# devtool.net
KiCad netlist of a schematic drawn in EAGLE
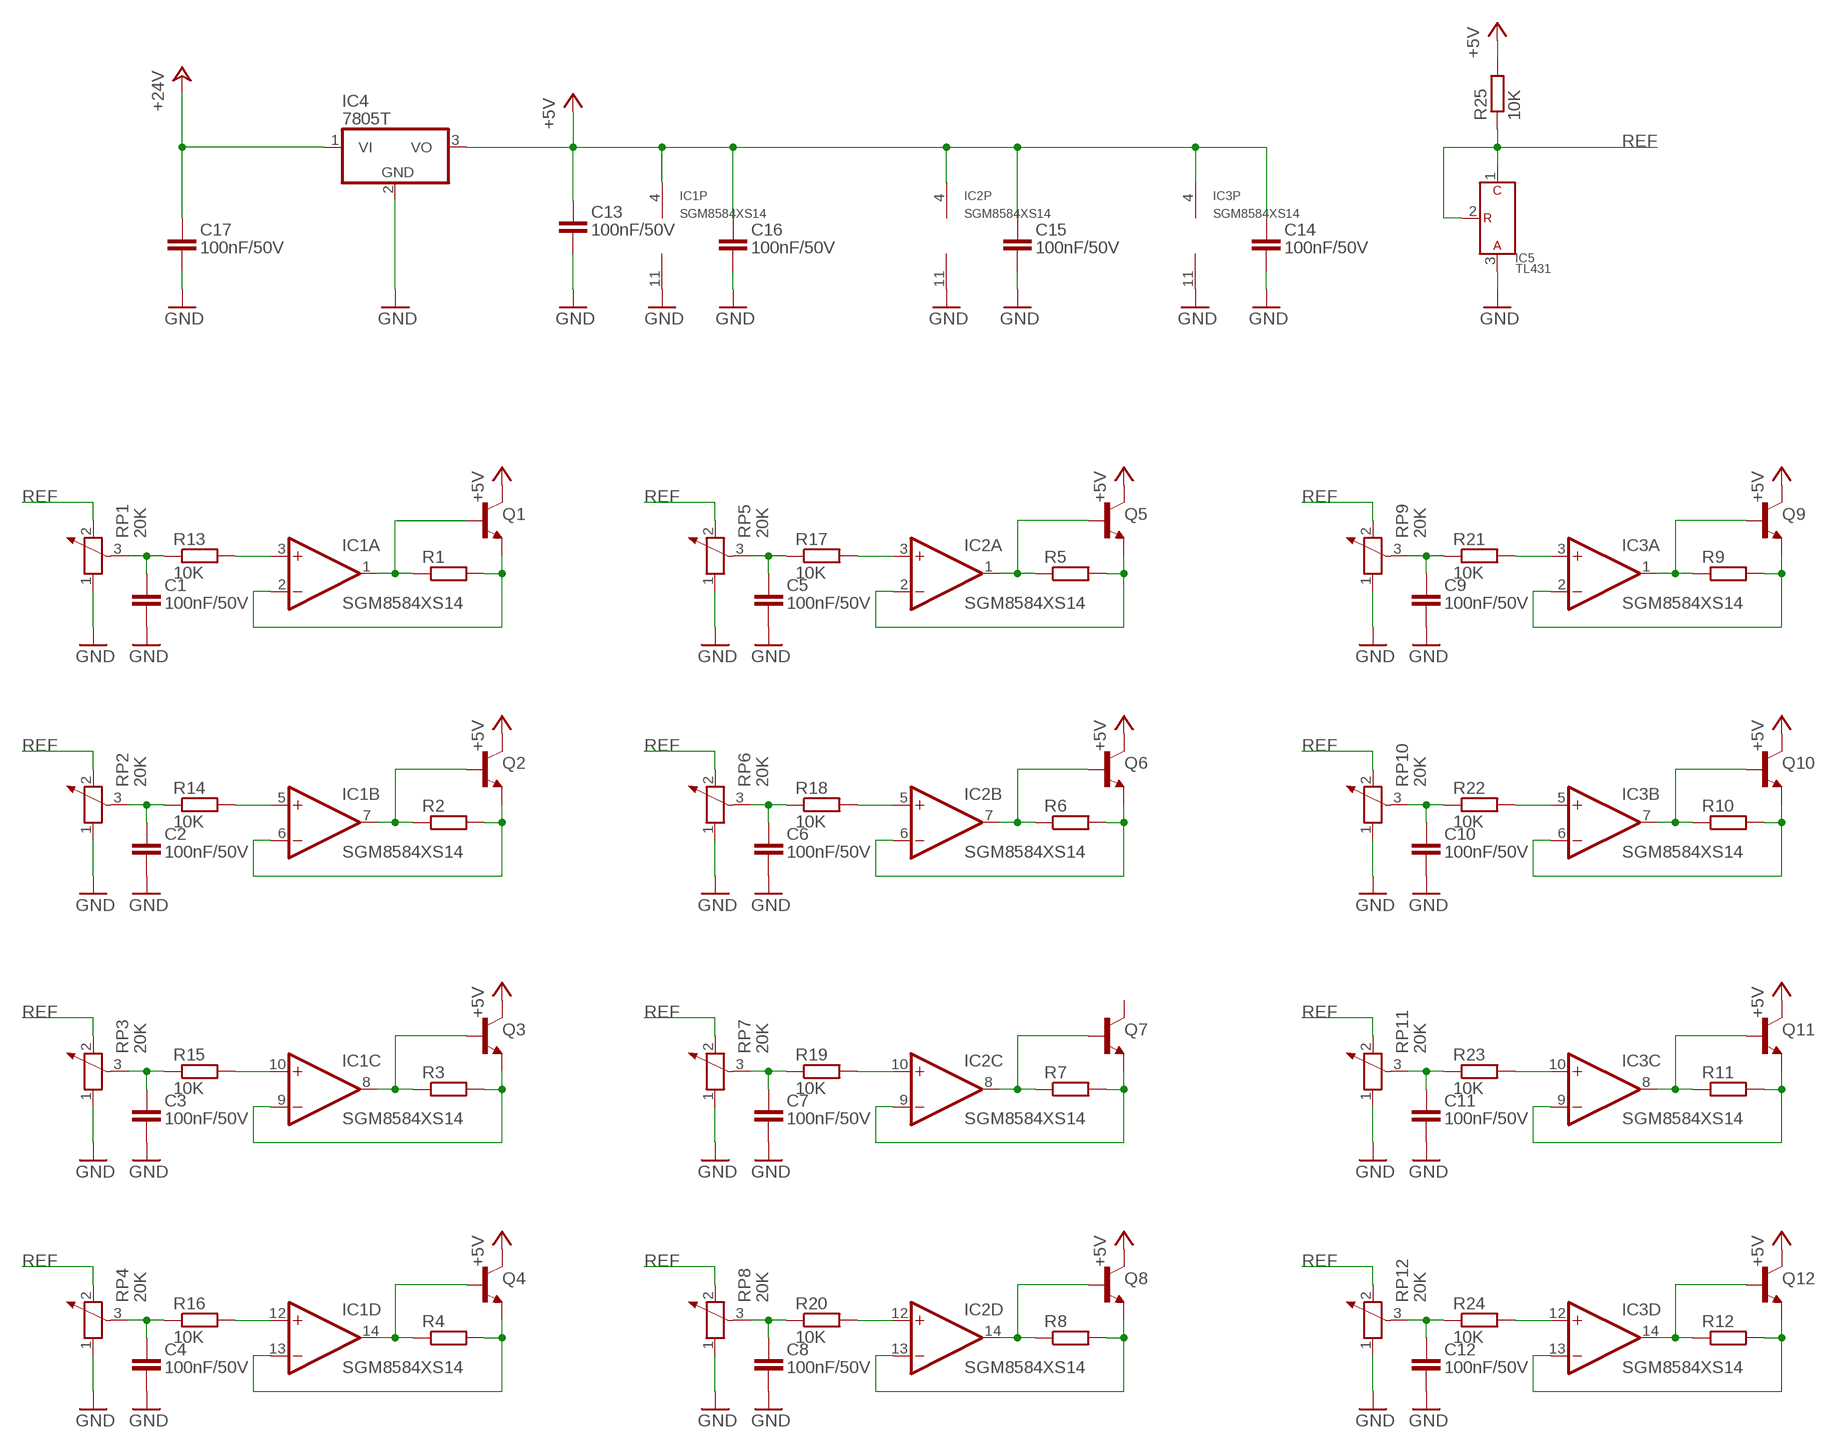
[diagram p0: schematic, sheet 1, part 1 of 2]
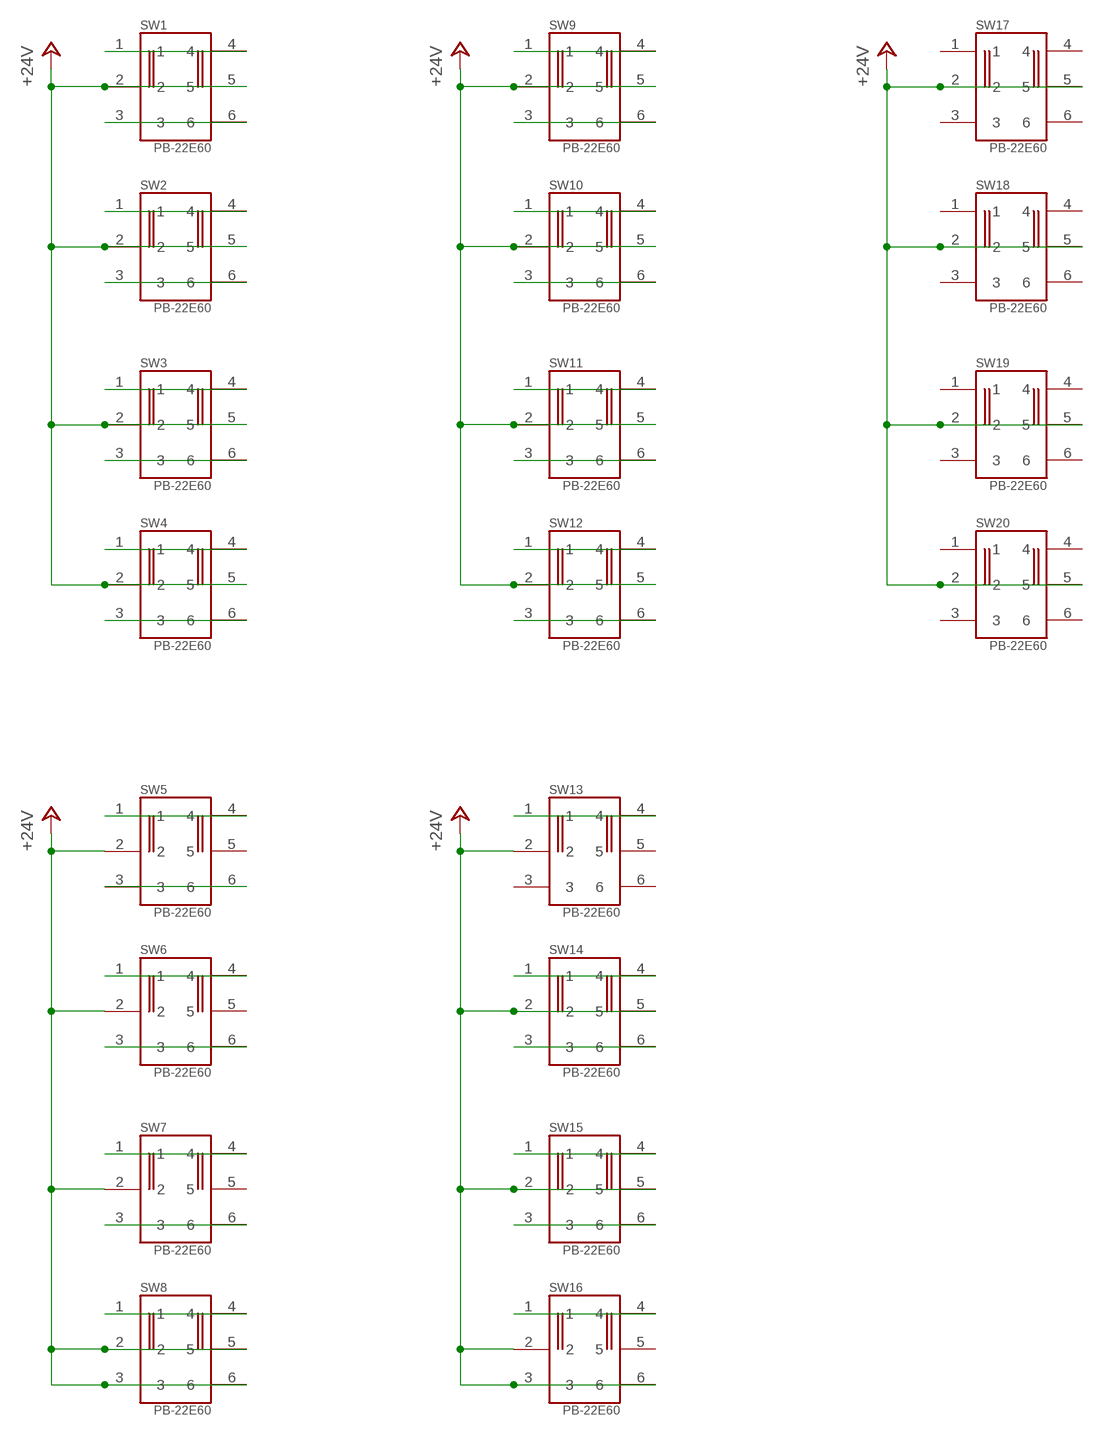
[diagram p1: schematic, sheet 1, part 2 of 2]

(export (version "E")
  (design (tool "Eeschema 10.0.6"))
  (components
    (comp (ref "C1")
      (value "100nF/50V")
      (footprint "eagle-import:C0603")
      (libsource (lib "eagle-import") (part "C0603"))
    )
    (comp (ref "C2")
      (value "100nF/50V")
      (footprint "eagle-import:C0603")
      (libsource (lib "eagle-import") (part "C0603"))
    )
    (comp (ref "C3")
      (value "100nF/50V")
      (footprint "eagle-import:C0603")
      (libsource (lib "eagle-import") (part "C0603"))
    )
    (comp (ref "C4")
      (value "100nF/50V")
      (footprint "eagle-import:C0603")
      (libsource (lib "eagle-import") (part "C0603"))
    )
    (comp (ref "C5")
      (value "100nF/50V")
      (footprint "eagle-import:C0603")
      (libsource (lib "eagle-import") (part "C0603"))
    )
    (comp (ref "C6")
      (value "100nF/50V")
      (footprint "eagle-import:C0603")
      (libsource (lib "eagle-import") (part "C0603"))
    )
    (comp (ref "C7")
      (value "100nF/50V")
      (footprint "eagle-import:C0603")
      (libsource (lib "eagle-import") (part "C0603"))
    )
    (comp (ref "C8")
      (value "100nF/50V")
      (footprint "eagle-import:C0603")
      (libsource (lib "eagle-import") (part "C0603"))
    )
    (comp (ref "C9")
      (value "100nF/50V")
      (footprint "eagle-import:C0603")
      (libsource (lib "eagle-import") (part "C0603"))
    )
    (comp (ref "C10")
      (value "100nF/50V")
      (footprint "eagle-import:C0603")
      (libsource (lib "eagle-import") (part "C0603"))
    )
    (comp (ref "C11")
      (value "100nF/50V")
      (footprint "eagle-import:C0603")
      (libsource (lib "eagle-import") (part "C0603"))
    )
    (comp (ref "C12")
      (value "100nF/50V")
      (footprint "eagle-import:C0603")
      (libsource (lib "eagle-import") (part "C0603"))
    )
    (comp (ref "C13")
      (value "100nF/50V")
      (footprint "eagle-import:C0603")
      (libsource (lib "eagle-import") (part "C0603"))
    )
    (comp (ref "C14")
      (value "100nF/50V")
      (footprint "eagle-import:C0603")
      (libsource (lib "eagle-import") (part "C0603"))
    )
    (comp (ref "C15")
      (value "100nF/50V")
      (footprint "eagle-import:C0603")
      (libsource (lib "eagle-import") (part "C0603"))
    )
    (comp (ref "C16")
      (value "100nF/50V")
      (footprint "eagle-import:C0603")
      (libsource (lib "eagle-import") (part "C0603"))
    )
    (comp (ref "C17")
      (value "100nF/50V")
      (footprint "eagle-import:C0603")
      (libsource (lib "eagle-import") (part "C0603"))
    )
    (comp (ref "IC1")
      (value "SGM8584XS14")
      (footprint "eagle-import:SOIC-14")
      (libsource (lib "eagle-import") (part "SGM8584XS14"))
    )
    (comp (ref "IC2")
      (value "SGM8584XS14")
      (footprint "eagle-import:SOIC-14")
      (libsource (lib "eagle-import") (part "SGM8584XS14"))
    )
    (comp (ref "IC3")
      (value "SGM8584XS14")
      (footprint "eagle-import:SOIC-14")
      (libsource (lib "eagle-import") (part "SGM8584XS14"))
    )
    (comp (ref "IC4")
      (value "7805T")
      (footprint "eagle-import:TO220H")
      (libsource (lib "eagle-import") (part "78T05"))
    )
    (comp (ref "IC5")
      (value "TL431")
      (footprint "eagle-import:SOT23-3")
      (libsource (lib "eagle-import") (part "TL431"))
    )
    (comp (ref "Q1")
      (value "NPN")
      (footprint "eagle-import:SOT23-BEC")
      (libsource (lib "eagle-import") (part "NPN"))
    )
    (comp (ref "Q2")
      (value "NPN")
      (footprint "eagle-import:SOT23-BEC")
      (libsource (lib "eagle-import") (part "NPN"))
    )
    (comp (ref "Q3")
      (value "NPN")
      (footprint "eagle-import:SOT23-BEC")
      (libsource (lib "eagle-import") (part "NPN"))
    )
    (comp (ref "Q4")
      (value "NPN")
      (footprint "eagle-import:SOT23-BEC")
      (libsource (lib "eagle-import") (part "NPN"))
    )
    (comp (ref "Q5")
      (value "NPN")
      (footprint "eagle-import:SOT23-BEC")
      (libsource (lib "eagle-import") (part "NPN"))
    )
    (comp (ref "Q6")
      (value "NPN")
      (footprint "eagle-import:SOT23-BEC")
      (libsource (lib "eagle-import") (part "NPN"))
    )
    (comp (ref "Q7")
      (value "NPN")
      (footprint "eagle-import:SOT23-BEC")
      (libsource (lib "eagle-import") (part "NPN"))
    )
    (comp (ref "Q8")
      (value "NPN")
      (footprint "eagle-import:SOT23-BEC")
      (libsource (lib "eagle-import") (part "NPN"))
    )
    (comp (ref "Q9")
      (value "NPN")
      (footprint "eagle-import:SOT23-BEC")
      (libsource (lib "eagle-import") (part "NPN"))
    )
    (comp (ref "Q10")
      (value "NPN")
      (footprint "eagle-import:SOT23-BEC")
      (libsource (lib "eagle-import") (part "NPN"))
    )
    (comp (ref "Q11")
      (value "NPN")
      (footprint "eagle-import:SOT23-BEC")
      (libsource (lib "eagle-import") (part "NPN"))
    )
    (comp (ref "Q12")
      (value "NPN")
      (footprint "eagle-import:SOT23-BEC")
      (libsource (lib "eagle-import") (part "NPN"))
    )
    (comp (ref "R1")
      (value "R0603")
      (footprint "eagle-import:R0603")
      (libsource (lib "eagle-import") (part "R0603"))
    )
    (comp (ref "R2")
      (value "R0603")
      (footprint "eagle-import:R0603")
      (libsource (lib "eagle-import") (part "R0603"))
    )
    (comp (ref "R3")
      (value "R0603")
      (footprint "eagle-import:R0603")
      (libsource (lib "eagle-import") (part "R0603"))
    )
    (comp (ref "R4")
      (value "R0603")
      (footprint "eagle-import:R0603")
      (libsource (lib "eagle-import") (part "R0603"))
    )
    (comp (ref "R5")
      (value "R0603")
      (footprint "eagle-import:R0603")
      (libsource (lib "eagle-import") (part "R0603"))
    )
    (comp (ref "R6")
      (value "R0603")
      (footprint "eagle-import:R0603")
      (libsource (lib "eagle-import") (part "R0603"))
    )
    (comp (ref "R7")
      (value "R0603")
      (footprint "eagle-import:R0603")
      (libsource (lib "eagle-import") (part "R0603"))
    )
    (comp (ref "R8")
      (value "R0603")
      (footprint "eagle-import:R0603")
      (libsource (lib "eagle-import") (part "R0603"))
    )
    (comp (ref "R9")
      (value "R0603")
      (footprint "eagle-import:R0603")
      (libsource (lib "eagle-import") (part "R0603"))
    )
    (comp (ref "R10")
      (value "R0603")
      (footprint "eagle-import:R0603")
      (libsource (lib "eagle-import") (part "R0603"))
    )
    (comp (ref "R11")
      (value "R0603")
      (footprint "eagle-import:R0603")
      (libsource (lib "eagle-import") (part "R0603"))
    )
    (comp (ref "R12")
      (value "R0603")
      (footprint "eagle-import:R0603")
      (libsource (lib "eagle-import") (part "R0603"))
    )
    (comp (ref "R13")
      (value "10K")
      (footprint "eagle-import:R0603")
      (libsource (lib "eagle-import") (part "R0603"))
    )
    (comp (ref "R14")
      (value "10K")
      (footprint "eagle-import:R0603")
      (libsource (lib "eagle-import") (part "R0603"))
    )
    (comp (ref "R15")
      (value "10K")
      (footprint "eagle-import:R0603")
      (libsource (lib "eagle-import") (part "R0603"))
    )
    (comp (ref "R16")
      (value "10K")
      (footprint "eagle-import:R0603")
      (libsource (lib "eagle-import") (part "R0603"))
    )
    (comp (ref "R17")
      (value "10K")
      (footprint "eagle-import:R0603")
      (libsource (lib "eagle-import") (part "R0603"))
    )
    (comp (ref "R18")
      (value "10K")
      (footprint "eagle-import:R0603")
      (libsource (lib "eagle-import") (part "R0603"))
    )
    (comp (ref "R19")
      (value "10K")
      (footprint "eagle-import:R0603")
      (libsource (lib "eagle-import") (part "R0603"))
    )
    (comp (ref "R20")
      (value "10K")
      (footprint "eagle-import:R0603")
      (libsource (lib "eagle-import") (part "R0603"))
    )
    (comp (ref "R21")
      (value "10K")
      (footprint "eagle-import:R0603")
      (libsource (lib "eagle-import") (part "R0603"))
    )
    (comp (ref "R22")
      (value "10K")
      (footprint "eagle-import:R0603")
      (libsource (lib "eagle-import") (part "R0603"))
    )
    (comp (ref "R23")
      (value "10K")
      (footprint "eagle-import:R0603")
      (libsource (lib "eagle-import") (part "R0603"))
    )
    (comp (ref "R24")
      (value "10K")
      (footprint "eagle-import:R0603")
      (libsource (lib "eagle-import") (part "R0603"))
    )
    (comp (ref "R25")
      (value "10K")
      (footprint "eagle-import:R0603")
      (libsource (lib "eagle-import") (part "R0603"))
    )
    (comp (ref "RP1")
      (value "20K")
      (footprint "eagle-import:RM065")
      (libsource (lib "eagle-import") (part "RM065"))
    )
    (comp (ref "RP2")
      (value "20K")
      (footprint "eagle-import:RM065")
      (libsource (lib "eagle-import") (part "RM065"))
    )
    (comp (ref "RP3")
      (value "20K")
      (footprint "eagle-import:RM065")
      (libsource (lib "eagle-import") (part "RM065"))
    )
    (comp (ref "RP4")
      (value "20K")
      (footprint "eagle-import:RM065")
      (libsource (lib "eagle-import") (part "RM065"))
    )
    (comp (ref "RP5")
      (value "20K")
      (footprint "eagle-import:RM065")
      (libsource (lib "eagle-import") (part "RM065"))
    )
    (comp (ref "RP6")
      (value "20K")
      (footprint "eagle-import:RM065")
      (libsource (lib "eagle-import") (part "RM065"))
    )
    (comp (ref "RP7")
      (value "20K")
      (footprint "eagle-import:RM065")
      (libsource (lib "eagle-import") (part "RM065"))
    )
    (comp (ref "RP8")
      (value "20K")
      (footprint "eagle-import:RM065")
      (libsource (lib "eagle-import") (part "RM065"))
    )
    (comp (ref "RP9")
      (value "20K")
      (footprint "eagle-import:RM065")
      (libsource (lib "eagle-import") (part "RM065"))
    )
    (comp (ref "RP10")
      (value "20K")
      (footprint "eagle-import:RM065")
      (libsource (lib "eagle-import") (part "RM065"))
    )
    (comp (ref "RP11")
      (value "20K")
      (footprint "eagle-import:RM065")
      (libsource (lib "eagle-import") (part "RM065"))
    )
    (comp (ref "RP12")
      (value "20K")
      (footprint "eagle-import:RM065")
      (libsource (lib "eagle-import") (part "RM065"))
    )
    (comp (ref "SW1")
      (value "PB-22E60")
      (footprint "eagle-import:PB-22E60")
      (libsource (lib "eagle-import") (part "PB-22E60"))
    )
    (comp (ref "SW2")
      (value "PB-22E60")
      (footprint "eagle-import:PB-22E60")
      (libsource (lib "eagle-import") (part "PB-22E60"))
    )
    (comp (ref "SW3")
      (value "PB-22E60")
      (footprint "eagle-import:PB-22E60")
      (libsource (lib "eagle-import") (part "PB-22E60"))
    )
    (comp (ref "SW4")
      (value "PB-22E60")
      (footprint "eagle-import:PB-22E60")
      (libsource (lib "eagle-import") (part "PB-22E60"))
    )
    (comp (ref "SW5")
      (value "PB-22E60")
      (footprint "eagle-import:PB-22E60")
      (libsource (lib "eagle-import") (part "PB-22E60"))
    )
    (comp (ref "SW6")
      (value "PB-22E60")
      (footprint "eagle-import:PB-22E60")
      (libsource (lib "eagle-import") (part "PB-22E60"))
    )
    (comp (ref "SW7")
      (value "PB-22E60")
      (footprint "eagle-import:PB-22E60")
      (libsource (lib "eagle-import") (part "PB-22E60"))
    )
    (comp (ref "SW8")
      (value "PB-22E60")
      (footprint "eagle-import:PB-22E60")
      (libsource (lib "eagle-import") (part "PB-22E60"))
    )
    (comp (ref "SW9")
      (value "PB-22E60")
      (footprint "eagle-import:PB-22E60")
      (libsource (lib "eagle-import") (part "PB-22E60"))
    )
    (comp (ref "SW10")
      (value "PB-22E60")
      (footprint "eagle-import:PB-22E60")
      (libsource (lib "eagle-import") (part "PB-22E60"))
    )
    (comp (ref "SW11")
      (value "PB-22E60")
      (footprint "eagle-import:PB-22E60")
      (libsource (lib "eagle-import") (part "PB-22E60"))
    )
    (comp (ref "SW12")
      (value "PB-22E60")
      (footprint "eagle-import:PB-22E60")
      (libsource (lib "eagle-import") (part "PB-22E60"))
    )
    (comp (ref "SW13")
      (value "PB-22E60")
      (footprint "eagle-import:PB-22E60")
      (libsource (lib "eagle-import") (part "PB-22E60"))
    )
    (comp (ref "SW14")
      (value "PB-22E60")
      (footprint "eagle-import:PB-22E60")
      (libsource (lib "eagle-import") (part "PB-22E60"))
    )
    (comp (ref "SW15")
      (value "PB-22E60")
      (footprint "eagle-import:PB-22E60")
      (libsource (lib "eagle-import") (part "PB-22E60"))
    )
    (comp (ref "SW16")
      (value "PB-22E60")
      (footprint "eagle-import:PB-22E60")
      (libsource (lib "eagle-import") (part "PB-22E60"))
    )
    (comp (ref "SW17")
      (value "PB-22E60")
      (footprint "eagle-import:PB-22E60")
      (libsource (lib "eagle-import") (part "PB-22E60"))
    )
    (comp (ref "SW18")
      (value "PB-22E60")
      (footprint "eagle-import:PB-22E60")
      (libsource (lib "eagle-import") (part "PB-22E60"))
    )
    (comp (ref "SW19")
      (value "PB-22E60")
      (footprint "eagle-import:PB-22E60")
      (libsource (lib "eagle-import") (part "PB-22E60"))
    )
    (comp (ref "SW20")
      (value "PB-22E60")
      (footprint "eagle-import:PB-22E60")
      (libsource (lib "eagle-import") (part "PB-22E60"))
    )
  )
  (nets
    (net (code "1") (name "+5V") (class "Default")
      (node (ref "C13") (pin "1") (pinfunction "1_1") (pintype "passive"))
      (node (ref "C14") (pin "1") (pinfunction "1_1") (pintype "passive"))
      (node (ref "C15") (pin "1") (pinfunction "1_1") (pintype "passive"))
      (node (ref "C16") (pin "1") (pinfunction "1_1") (pintype "passive"))
      (node (ref "IC1") (pin "4") (pinfunction "V+_4") (pintype "power_in"))
      (node (ref "IC2") (pin "4") (pinfunction "V+_4") (pintype "power_in"))
      (node (ref "IC3") (pin "4") (pinfunction "V+_4") (pintype "power_in"))
      (node (ref "IC4") (pin "3") (pinfunction "VO_3") (pintype "passive"))
      (node (ref "Q1") (pin "C") (pinfunction "C_C") (pintype "passive"))
      (node (ref "Q10") (pin "C") (pinfunction "C_C") (pintype "passive"))
      (node (ref "Q11") (pin "C") (pinfunction "C_C") (pintype "passive"))
      (node (ref "Q12") (pin "C") (pinfunction "C_C") (pintype "passive"))
      (node (ref "Q2") (pin "C") (pinfunction "C_C") (pintype "passive"))
      (node (ref "Q3") (pin "C") (pinfunction "C_C") (pintype "passive"))
      (node (ref "Q4") (pin "C") (pinfunction "C_C") (pintype "passive"))
      (node (ref "Q5") (pin "C") (pinfunction "C_C") (pintype "passive"))
      (node (ref "Q6") (pin "C") (pinfunction "C_C") (pintype "passive"))
      (node (ref "Q8") (pin "C") (pinfunction "C_C") (pintype "passive"))
      (node (ref "Q9") (pin "C") (pinfunction "C_C") (pintype "passive"))
      (node (ref "R25") (pin "2") (pinfunction "2_2") (pintype "passive"))
    )
    (net (code "2") (name "+24V") (class "Default")
      (node (ref "C17") (pin "1") (pinfunction "1_1") (pintype "passive"))
      (node (ref "IC4") (pin "1") (pinfunction "VI_1") (pintype "input"))
      (node (ref "SW1") (pin "2") (pinfunction "2_2") (pintype "passive"))
      (node (ref "SW1") (pin "5") (pinfunction "5_5") (pintype "passive"))
      (node (ref "SW10") (pin "2") (pinfunction "2_2") (pintype "passive"))
      (node (ref "SW10") (pin "5") (pinfunction "5_5") (pintype "passive"))
      (node (ref "SW11") (pin "2") (pinfunction "2_2") (pintype "passive"))
      (node (ref "SW11") (pin "5") (pinfunction "5_5") (pintype "passive"))
      (node (ref "SW12") (pin "2") (pinfunction "2_2") (pintype "passive"))
      (node (ref "SW12") (pin "5") (pinfunction "5_5") (pintype "passive"))
      (node (ref "SW13") (pin "2") (pinfunction "2_2") (pintype "passive"))
      (node (ref "SW14") (pin "2") (pinfunction "2_2") (pintype "passive"))
      (node (ref "SW14") (pin "5") (pinfunction "5_5") (pintype "passive"))
      (node (ref "SW15") (pin "2") (pinfunction "2_2") (pintype "passive"))
      (node (ref "SW15") (pin "5") (pinfunction "5_5") (pintype "passive"))
      (node (ref "SW16") (pin "2") (pinfunction "2_2") (pintype "passive"))
      (node (ref "SW16") (pin "3") (pinfunction "3_3") (pintype "passive"))
      (node (ref "SW16") (pin "6") (pinfunction "6_6") (pintype "passive"))
      (node (ref "SW17") (pin "2") (pinfunction "2_2") (pintype "passive"))
      (node (ref "SW17") (pin "5") (pinfunction "5_5") (pintype "passive"))
      (node (ref "SW18") (pin "2") (pinfunction "2_2") (pintype "passive"))
      (node (ref "SW18") (pin "5") (pinfunction "5_5") (pintype "passive"))
      (node (ref "SW19") (pin "2") (pinfunction "2_2") (pintype "passive"))
      (node (ref "SW19") (pin "5") (pinfunction "5_5") (pintype "passive"))
      (node (ref "SW2") (pin "2") (pinfunction "2_2") (pintype "passive"))
      (node (ref "SW2") (pin "5") (pinfunction "5_5") (pintype "passive"))
      (node (ref "SW20") (pin "2") (pinfunction "2_2") (pintype "passive"))
      (node (ref "SW20") (pin "5") (pinfunction "5_5") (pintype "passive"))
      (node (ref "SW3") (pin "2") (pinfunction "2_2") (pintype "passive"))
      (node (ref "SW3") (pin "5") (pinfunction "5_5") (pintype "passive"))
      (node (ref "SW4") (pin "2") (pinfunction "2_2") (pintype "passive"))
      (node (ref "SW4") (pin "5") (pinfunction "5_5") (pintype "passive"))
      (node (ref "SW5") (pin "2") (pinfunction "2_2") (pintype "passive"))
      (node (ref "SW6") (pin "2") (pinfunction "2_2") (pintype "passive"))
      (node (ref "SW7") (pin "2") (pinfunction "2_2") (pintype "passive"))
      (node (ref "SW8") (pin "2") (pinfunction "2_2") (pintype "passive"))
      (node (ref "SW8") (pin "3") (pinfunction "3_3") (pintype "passive"))
      (node (ref "SW8") (pin "5") (pinfunction "5_5") (pintype "passive"))
      (node (ref "SW8") (pin "6") (pinfunction "6_6") (pintype "passive"))
      (node (ref "SW9") (pin "2") (pinfunction "2_2") (pintype "passive"))
      (node (ref "SW9") (pin "5") (pinfunction "5_5") (pintype "passive"))
    )
    (net (code "3") (name "/REF") (class "Default")
      (node (ref "IC5") (pin "1") (pinfunction "C_1") (pintype "passive"))
      (node (ref "IC5") (pin "2") (pinfunction "REF_2") (pintype "passive"))
      (node (ref "R25") (pin "1") (pinfunction "1_1") (pintype "passive"))
      (node (ref "RP1") (pin "2") (pinfunction "2_2") (pintype "passive"))
      (node (ref "RP10") (pin "2") (pinfunction "2_2") (pintype "passive"))
      (node (ref "RP11") (pin "2") (pinfunction "2_2") (pintype "passive"))
      (node (ref "RP12") (pin "2") (pinfunction "2_2") (pintype "passive"))
      (node (ref "RP2") (pin "2") (pinfunction "2_2") (pintype "passive"))
      (node (ref "RP3") (pin "2") (pinfunction "2_2") (pintype "passive"))
      (node (ref "RP4") (pin "2") (pinfunction "2_2") (pintype "passive"))
      (node (ref "RP5") (pin "2") (pinfunction "2_2") (pintype "passive"))
      (node (ref "RP6") (pin "2") (pinfunction "2_2") (pintype "passive"))
      (node (ref "RP7") (pin "2") (pinfunction "2_2") (pintype "passive"))
      (node (ref "RP8") (pin "2") (pinfunction "2_2") (pintype "passive"))
      (node (ref "RP9") (pin "2") (pinfunction "2_2") (pintype "passive"))
    )
    (net (code "4") (name "GND") (class "Default")
      (node (ref "C1") (pin "2") (pinfunction "2_2") (pintype "passive"))
      (node (ref "C10") (pin "2") (pinfunction "2_2") (pintype "passive"))
      (node (ref "C11") (pin "2") (pinfunction "2_2") (pintype "passive"))
      (node (ref "C12") (pin "2") (pinfunction "2_2") (pintype "passive"))
      (node (ref "C13") (pin "2") (pinfunction "2_2") (pintype "passive"))
      (node (ref "C14") (pin "2") (pinfunction "2_2") (pintype "passive"))
      (node (ref "C15") (pin "2") (pinfunction "2_2") (pintype "passive"))
      (node (ref "C16") (pin "2") (pinfunction "2_2") (pintype "passive"))
      (node (ref "C17") (pin "2") (pinfunction "2_2") (pintype "passive"))
      (node (ref "C2") (pin "2") (pinfunction "2_2") (pintype "passive"))
      (node (ref "C3") (pin "2") (pinfunction "2_2") (pintype "passive"))
      (node (ref "C4") (pin "2") (pinfunction "2_2") (pintype "passive"))
      (node (ref "C5") (pin "2") (pinfunction "2_2") (pintype "passive"))
      (node (ref "C6") (pin "2") (pinfunction "2_2") (pintype "passive"))
      (node (ref "C7") (pin "2") (pinfunction "2_2") (pintype "passive"))
      (node (ref "C8") (pin "2") (pinfunction "2_2") (pintype "passive"))
      (node (ref "C9") (pin "2") (pinfunction "2_2") (pintype "passive"))
      (node (ref "IC1") (pin "11") (pinfunction "V-_11") (pintype "power_in"))
      (node (ref "IC2") (pin "11") (pinfunction "V-_11") (pintype "power_in"))
      (node (ref "IC3") (pin "11") (pinfunction "V-_11") (pintype "power_in"))
      (node (ref "IC4") (pin "2") (pinfunction "GND_2") (pintype "passive"))
      (node (ref "IC5") (pin "3") (pinfunction "A_3") (pintype "passive"))
      (node (ref "RP1") (pin "1") (pinfunction "1_1") (pintype "passive"))
      (node (ref "RP10") (pin "1") (pinfunction "1_1") (pintype "passive"))
      (node (ref "RP11") (pin "1") (pinfunction "1_1") (pintype "passive"))
      (node (ref "RP12") (pin "1") (pinfunction "1_1") (pintype "passive"))
      (node (ref "RP2") (pin "1") (pinfunction "1_1") (pintype "passive"))
      (node (ref "RP3") (pin "1") (pinfunction "1_1") (pintype "passive"))
      (node (ref "RP4") (pin "1") (pinfunction "1_1") (pintype "passive"))
      (node (ref "RP5") (pin "1") (pinfunction "1_1") (pintype "passive"))
      (node (ref "RP6") (pin "1") (pinfunction "1_1") (pintype "passive"))
      (node (ref "RP7") (pin "1") (pinfunction "1_1") (pintype "passive"))
      (node (ref "RP8") (pin "1") (pinfunction "1_1") (pintype "passive"))
      (node (ref "RP9") (pin "1") (pinfunction "1_1") (pintype "passive"))
    )
    (net (code "5") (name "Net-(C1-Pad1)") (class "Default")
      (node (ref "C1") (pin "1") (pinfunction "1_1") (pintype "passive"))
      (node (ref "R13") (pin "1") (pinfunction "1_1") (pintype "passive"))
      (node (ref "RP1") (pin "3") (pinfunction "3_3") (pintype "passive"))
    )
    (net (code "6") (name "Net-(C2-Pad1)") (class "Default")
      (node (ref "C2") (pin "1") (pinfunction "1_1") (pintype "passive"))
      (node (ref "R14") (pin "1") (pinfunction "1_1") (pintype "passive"))
      (node (ref "RP2") (pin "3") (pinfunction "3_3") (pintype "passive"))
    )
    (net (code "7") (name "Net-(C3-Pad1)") (class "Default")
      (node (ref "C3") (pin "1") (pinfunction "1_1") (pintype "passive"))
      (node (ref "R15") (pin "1") (pinfunction "1_1") (pintype "passive"))
      (node (ref "RP3") (pin "3") (pinfunction "3_3") (pintype "passive"))
    )
    (net (code "8") (name "Net-(C4-Pad1)") (class "Default")
      (node (ref "C4") (pin "1") (pinfunction "1_1") (pintype "passive"))
      (node (ref "R16") (pin "1") (pinfunction "1_1") (pintype "passive"))
      (node (ref "RP4") (pin "3") (pinfunction "3_3") (pintype "passive"))
    )
    (net (code "9") (name "Net-(C5-Pad1)") (class "Default")
      (node (ref "C5") (pin "1") (pinfunction "1_1") (pintype "passive"))
      (node (ref "R17") (pin "1") (pinfunction "1_1") (pintype "passive"))
      (node (ref "RP5") (pin "3") (pinfunction "3_3") (pintype "passive"))
    )
    (net (code "10") (name "Net-(C6-Pad1)") (class "Default")
      (node (ref "C6") (pin "1") (pinfunction "1_1") (pintype "passive"))
      (node (ref "R18") (pin "1") (pinfunction "1_1") (pintype "passive"))
      (node (ref "RP6") (pin "3") (pinfunction "3_3") (pintype "passive"))
    )
    (net (code "11") (name "Net-(C7-Pad1)") (class "Default")
      (node (ref "C7") (pin "1") (pinfunction "1_1") (pintype "passive"))
      (node (ref "R19") (pin "1") (pinfunction "1_1") (pintype "passive"))
      (node (ref "RP7") (pin "3") (pinfunction "3_3") (pintype "passive"))
    )
    (net (code "12") (name "Net-(C8-Pad1)") (class "Default")
      (node (ref "C8") (pin "1") (pinfunction "1_1") (pintype "passive"))
      (node (ref "R20") (pin "1") (pinfunction "1_1") (pintype "passive"))
      (node (ref "RP8") (pin "3") (pinfunction "3_3") (pintype "passive"))
    )
    (net (code "13") (name "Net-(C9-Pad1)") (class "Default")
      (node (ref "C9") (pin "1") (pinfunction "1_1") (pintype "passive"))
      (node (ref "R21") (pin "1") (pinfunction "1_1") (pintype "passive"))
      (node (ref "RP9") (pin "3") (pinfunction "3_3") (pintype "passive"))
    )
    (net (code "14") (name "Net-(C10-Pad1)") (class "Default")
      (node (ref "C10") (pin "1") (pinfunction "1_1") (pintype "passive"))
      (node (ref "R22") (pin "1") (pinfunction "1_1") (pintype "passive"))
      (node (ref "RP10") (pin "3") (pinfunction "3_3") (pintype "passive"))
    )
    (net (code "15") (name "Net-(C11-Pad1)") (class "Default")
      (node (ref "C11") (pin "1") (pinfunction "1_1") (pintype "passive"))
      (node (ref "R23") (pin "1") (pinfunction "1_1") (pintype "passive"))
      (node (ref "RP11") (pin "3") (pinfunction "3_3") (pintype "passive"))
    )
    (net (code "16") (name "Net-(C12-Pad1)") (class "Default")
      (node (ref "C12") (pin "1") (pinfunction "1_1") (pintype "passive"))
      (node (ref "R24") (pin "1") (pinfunction "1_1") (pintype "passive"))
      (node (ref "RP12") (pin "3") (pinfunction "3_3") (pintype "passive"))
    )
    (net (code "17") (name "Net-(IC1A-+IN)") (class "Default")
      (node (ref "IC1") (pin "3") (pinfunction "+IN_3") (pintype "input"))
      (node (ref "R13") (pin "2") (pinfunction "2_2") (pintype "passive"))
    )
    (net (code "18") (name "Net-(IC1A--IN)") (class "Default")
      (node (ref "IC1") (pin "2") (pinfunction "-IN_2") (pintype "input"))
      (node (ref "Q1") (pin "E") (pinfunction "E_E") (pintype "passive"))
      (node (ref "R1") (pin "2") (pinfunction "2_2") (pintype "passive"))
    )
    (net (code "19") (name "Net-(IC1A-OUT)") (class "Default")
      (node (ref "IC1") (pin "1") (pinfunction "OUT_1") (pintype "output"))
      (node (ref "Q1") (pin "B") (pinfunction "B_B") (pintype "passive"))
      (node (ref "R1") (pin "1") (pinfunction "1_1") (pintype "passive"))
    )
    (net (code "20") (name "Net-(IC1B-+IN)") (class "Default")
      (node (ref "IC1") (pin "5") (pinfunction "+IN_5") (pintype "input"))
      (node (ref "R14") (pin "2") (pinfunction "2_2") (pintype "passive"))
    )
    (net (code "21") (name "Net-(IC1B--IN)") (class "Default")
      (node (ref "IC1") (pin "6") (pinfunction "-IN_6") (pintype "input"))
      (node (ref "Q2") (pin "E") (pinfunction "E_E") (pintype "passive"))
      (node (ref "R2") (pin "2") (pinfunction "2_2") (pintype "passive"))
    )
    (net (code "22") (name "Net-(IC1B-OUT)") (class "Default")
      (node (ref "IC1") (pin "7") (pinfunction "OUT_7") (pintype "output"))
      (node (ref "Q2") (pin "B") (pinfunction "B_B") (pintype "passive"))
      (node (ref "R2") (pin "1") (pinfunction "1_1") (pintype "passive"))
    )
    (net (code "23") (name "Net-(IC1C-+IN)") (class "Default")
      (node (ref "IC1") (pin "10") (pinfunction "+IN_10") (pintype "input"))
      (node (ref "R15") (pin "2") (pinfunction "2_2") (pintype "passive"))
    )
    (net (code "24") (name "Net-(IC1C--IN)") (class "Default")
      (node (ref "IC1") (pin "9") (pinfunction "-IN_9") (pintype "input"))
      (node (ref "Q3") (pin "E") (pinfunction "E_E") (pintype "passive"))
      (node (ref "R3") (pin "2") (pinfunction "2_2") (pintype "passive"))
    )
    (net (code "25") (name "Net-(IC1C-OUT)") (class "Default")
      (node (ref "IC1") (pin "8") (pinfunction "OUT_8") (pintype "output"))
      (node (ref "Q3") (pin "B") (pinfunction "B_B") (pintype "passive"))
      (node (ref "R3") (pin "1") (pinfunction "1_1") (pintype "passive"))
    )
    (net (code "26") (name "Net-(IC1D-+IN)") (class "Default")
      (node (ref "IC1") (pin "12") (pinfunction "+IN_12") (pintype "input"))
      (node (ref "R16") (pin "2") (pinfunction "2_2") (pintype "passive"))
    )
    (net (code "27") (name "Net-(IC1D--IN)") (class "Default")
      (node (ref "IC1") (pin "13") (pinfunction "-IN_13") (pintype "input"))
      (node (ref "Q4") (pin "E") (pinfunction "E_E") (pintype "passive"))
      (node (ref "R4") (pin "2") (pinfunction "2_2") (pintype "passive"))
    )
    (net (code "28") (name "Net-(IC1D-OUT)") (class "Default")
      (node (ref "IC1") (pin "14") (pinfunction "OUT_14") (pintype "output"))
      (node (ref "Q4") (pin "B") (pinfunction "B_B") (pintype "passive"))
      (node (ref "R4") (pin "1") (pinfunction "1_1") (pintype "passive"))
    )
    (net (code "29") (name "Net-(IC2A-+IN)") (class "Default")
      (node (ref "IC2") (pin "3") (pinfunction "+IN_3") (pintype "input"))
      (node (ref "R17") (pin "2") (pinfunction "2_2") (pintype "passive"))
    )
    (net (code "30") (name "Net-(IC2A--IN)") (class "Default")
      (node (ref "IC2") (pin "2") (pinfunction "-IN_2") (pintype "input"))
      (node (ref "Q5") (pin "E") (pinfunction "E_E") (pintype "passive"))
      (node (ref "R5") (pin "2") (pinfunction "2_2") (pintype "passive"))
    )
    (net (code "31") (name "Net-(IC2A-OUT)") (class "Default")
      (node (ref "IC2") (pin "1") (pinfunction "OUT_1") (pintype "output"))
      (node (ref "Q5") (pin "B") (pinfunction "B_B") (pintype "passive"))
      (node (ref "R5") (pin "1") (pinfunction "1_1") (pintype "passive"))
    )
    (net (code "32") (name "Net-(IC2B-+IN)") (class "Default")
      (node (ref "IC2") (pin "5") (pinfunction "+IN_5") (pintype "input"))
      (node (ref "R18") (pin "2") (pinfunction "2_2") (pintype "passive"))
    )
    (net (code "33") (name "Net-(IC2B--IN)") (class "Default")
      (node (ref "IC2") (pin "6") (pinfunction "-IN_6") (pintype "input"))
      (node (ref "Q6") (pin "E") (pinfunction "E_E") (pintype "passive"))
      (node (ref "R6") (pin "2") (pinfunction "2_2") (pintype "passive"))
    )
    (net (code "34") (name "Net-(IC2B-OUT)") (class "Default")
      (node (ref "IC2") (pin "7") (pinfunction "OUT_7") (pintype "output"))
      (node (ref "Q6") (pin "B") (pinfunction "B_B") (pintype "passive"))
      (node (ref "R6") (pin "1") (pinfunction "1_1") (pintype "passive"))
    )
    (net (code "35") (name "Net-(IC2C-+IN)") (class "Default")
      (node (ref "IC2") (pin "10") (pinfunction "+IN_10") (pintype "input"))
      (node (ref "R19") (pin "2") (pinfunction "2_2") (pintype "passive"))
    )
    (net (code "36") (name "Net-(IC2C--IN)") (class "Default")
      (node (ref "IC2") (pin "9") (pinfunction "-IN_9") (pintype "input"))
      (node (ref "Q7") (pin "E") (pinfunction "E_E") (pintype "passive"))
      (node (ref "R7") (pin "2") (pinfunction "2_2") (pintype "passive"))
    )
    (net (code "37") (name "Net-(IC2C-OUT)") (class "Default")
      (node (ref "IC2") (pin "8") (pinfunction "OUT_8") (pintype "output"))
      (node (ref "Q7") (pin "B") (pinfunction "B_B") (pintype "passive"))
      (node (ref "R7") (pin "1") (pinfunction "1_1") (pintype "passive"))
    )
    (net (code "38") (name "Net-(IC2D-+IN)") (class "Default")
      (node (ref "IC2") (pin "12") (pinfunction "+IN_12") (pintype "input"))
      (node (ref "R20") (pin "2") (pinfunction "2_2") (pintype "passive"))
    )
    (net (code "39") (name "Net-(IC2D--IN)") (class "Default")
      (node (ref "IC2") (pin "13") (pinfunction "-IN_13") (pintype "input"))
      (node (ref "Q8") (pin "E") (pinfunction "E_E") (pintype "passive"))
      (node (ref "R8") (pin "2") (pinfunction "2_2") (pintype "passive"))
    )
    (net (code "40") (name "Net-(IC2D-OUT)") (class "Default")
      (node (ref "IC2") (pin "14") (pinfunction "OUT_14") (pintype "output"))
      (node (ref "Q8") (pin "B") (pinfunction "B_B") (pintype "passive"))
      (node (ref "R8") (pin "1") (pinfunction "1_1") (pintype "passive"))
    )
    (net (code "41") (name "Net-(IC3A-+IN)") (class "Default")
      (node (ref "IC3") (pin "3") (pinfunction "+IN_3") (pintype "input"))
      (node (ref "R21") (pin "2") (pinfunction "2_2") (pintype "passive"))
    )
    (net (code "42") (name "Net-(IC3A--IN)") (class "Default")
      (node (ref "IC3") (pin "2") (pinfunction "-IN_2") (pintype "input"))
      (node (ref "Q9") (pin "E") (pinfunction "E_E") (pintype "passive"))
      (node (ref "R9") (pin "2") (pinfunction "2_2") (pintype "passive"))
    )
    (net (code "43") (name "Net-(IC3A-OUT)") (class "Default")
      (node (ref "IC3") (pin "1") (pinfunction "OUT_1") (pintype "output"))
      (node (ref "Q9") (pin "B") (pinfunction "B_B") (pintype "passive"))
      (node (ref "R9") (pin "1") (pinfunction "1_1") (pintype "passive"))
    )
    (net (code "44") (name "Net-(IC3B-+IN)") (class "Default")
      (node (ref "IC3") (pin "5") (pinfunction "+IN_5") (pintype "input"))
      (node (ref "R22") (pin "2") (pinfunction "2_2") (pintype "passive"))
    )
    (net (code "45") (name "Net-(IC3B--IN)") (class "Default")
      (node (ref "IC3") (pin "6") (pinfunction "-IN_6") (pintype "input"))
      (node (ref "Q10") (pin "E") (pinfunction "E_E") (pintype "passive"))
      (node (ref "R10") (pin "2") (pinfunction "2_2") (pintype "passive"))
    )
    (net (code "46") (name "Net-(IC3B-OUT)") (class "Default")
      (node (ref "IC3") (pin "7") (pinfunction "OUT_7") (pintype "output"))
      (node (ref "Q10") (pin "B") (pinfunction "B_B") (pintype "passive"))
      (node (ref "R10") (pin "1") (pinfunction "1_1") (pintype "passive"))
    )
    (net (code "47") (name "Net-(IC3C-+IN)") (class "Default")
      (node (ref "IC3") (pin "10") (pinfunction "+IN_10") (pintype "input"))
      (node (ref "R23") (pin "2") (pinfunction "2_2") (pintype "passive"))
    )
    (net (code "48") (name "Net-(IC3C--IN)") (class "Default")
      (node (ref "IC3") (pin "9") (pinfunction "-IN_9") (pintype "input"))
      (node (ref "Q11") (pin "E") (pinfunction "E_E") (pintype "passive"))
      (node (ref "R11") (pin "2") (pinfunction "2_2") (pintype "passive"))
    )
    (net (code "49") (name "Net-(IC3C-OUT)") (class "Default")
      (node (ref "IC3") (pin "8") (pinfunction "OUT_8") (pintype "output"))
      (node (ref "Q11") (pin "B") (pinfunction "B_B") (pintype "passive"))
      (node (ref "R11") (pin "1") (pinfunction "1_1") (pintype "passive"))
    )
    (net (code "50") (name "Net-(IC3D-+IN)") (class "Default")
      (node (ref "IC3") (pin "12") (pinfunction "+IN_12") (pintype "input"))
      (node (ref "R24") (pin "2") (pinfunction "2_2") (pintype "passive"))
    )
    (net (code "51") (name "Net-(IC3D--IN)") (class "Default")
      (node (ref "IC3") (pin "13") (pinfunction "-IN_13") (pintype "input"))
      (node (ref "Q12") (pin "E") (pinfunction "E_E") (pintype "passive"))
      (node (ref "R12") (pin "2") (pinfunction "2_2") (pintype "passive"))
    )
    (net (code "52") (name "Net-(IC3D-OUT)") (class "Default")
      (node (ref "IC3") (pin "14") (pinfunction "OUT_14") (pintype "output"))
      (node (ref "Q12") (pin "B") (pinfunction "B_B") (pintype "passive"))
      (node (ref "R12") (pin "1") (pinfunction "1_1") (pintype "passive"))
    )
    (net (code "53") (name "Net-(SW1-Pad1)") (class "Default")
      (node (ref "SW1") (pin "1") (pinfunction "1_1") (pintype "passive"))
      (node (ref "SW1") (pin "4") (pinfunction "4_4") (pintype "passive"))
    )
    (net (code "54") (name "Net-(SW1-Pad3)") (class "Default")
      (node (ref "SW1") (pin "3") (pinfunction "3_3") (pintype "passive"))
      (node (ref "SW1") (pin "6") (pinfunction "6_6") (pintype "passive"))
    )
    (net (code "55") (name "Net-(SW2-Pad1)") (class "Default")
      (node (ref "SW2") (pin "1") (pinfunction "1_1") (pintype "passive"))
      (node (ref "SW2") (pin "4") (pinfunction "4_4") (pintype "passive"))
    )
    (net (code "56") (name "Net-(SW2-Pad3)") (class "Default")
      (node (ref "SW2") (pin "3") (pinfunction "3_3") (pintype "passive"))
      (node (ref "SW2") (pin "6") (pinfunction "6_6") (pintype "passive"))
    )
    (net (code "57") (name "Net-(SW3-Pad1)") (class "Default")
      (node (ref "SW3") (pin "1") (pinfunction "1_1") (pintype "passive"))
      (node (ref "SW3") (pin "4") (pinfunction "4_4") (pintype "passive"))
    )
    (net (code "58") (name "Net-(SW3-Pad3)") (class "Default")
      (node (ref "SW3") (pin "3") (pinfunction "3_3") (pintype "passive"))
      (node (ref "SW3") (pin "6") (pinfunction "6_6") (pintype "passive"))
    )
    (net (code "59") (name "Net-(SW4-Pad1)") (class "Default")
      (node (ref "SW4") (pin "1") (pinfunction "1_1") (pintype "passive"))
      (node (ref "SW4") (pin "4") (pinfunction "4_4") (pintype "passive"))
    )
    (net (code "60") (name "Net-(SW4-Pad3)") (class "Default")
      (node (ref "SW4") (pin "3") (pinfunction "3_3") (pintype "passive"))
      (node (ref "SW4") (pin "6") (pinfunction "6_6") (pintype "passive"))
    )
    (net (code "61") (name "Net-(SW5-Pad1)") (class "Default")
      (node (ref "SW5") (pin "1") (pinfunction "1_1") (pintype "passive"))
      (node (ref "SW5") (pin "4") (pinfunction "4_4") (pintype "passive"))
    )
    (net (code "62") (name "Net-(SW5-Pad3)") (class "Default")
      (node (ref "SW5") (pin "3") (pinfunction "3_3") (pintype "passive"))
      (node (ref "SW5") (pin "6") (pinfunction "6_6") (pintype "passive"))
    )
    (net (code "63") (name "Net-(SW6-Pad1)") (class "Default")
      (node (ref "SW6") (pin "1") (pinfunction "1_1") (pintype "passive"))
      (node (ref "SW6") (pin "4") (pinfunction "4_4") (pintype "passive"))
    )
    (net (code "64") (name "Net-(SW6-Pad3)") (class "Default")
      (node (ref "SW6") (pin "3") (pinfunction "3_3") (pintype "passive"))
      (node (ref "SW6") (pin "6") (pinfunction "6_6") (pintype "passive"))
    )
    (net (code "65") (name "Net-(SW7-Pad1)") (class "Default")
      (node (ref "SW7") (pin "1") (pinfunction "1_1") (pintype "passive"))
      (node (ref "SW7") (pin "4") (pinfunction "4_4") (pintype "passive"))
    )
    (net (code "66") (name "Net-(SW7-Pad3)") (class "Default")
      (node (ref "SW7") (pin "3") (pinfunction "3_3") (pintype "passive"))
      (node (ref "SW7") (pin "6") (pinfunction "6_6") (pintype "passive"))
    )
    (net (code "67") (name "Net-(SW8-Pad1)") (class "Default")
      (node (ref "SW8") (pin "1") (pinfunction "1_1") (pintype "passive"))
      (node (ref "SW8") (pin "4") (pinfunction "4_4") (pintype "passive"))
    )
    (net (code "68") (name "Net-(SW9-Pad1)") (class "Default")
      (node (ref "SW9") (pin "1") (pinfunction "1_1") (pintype "passive"))
      (node (ref "SW9") (pin "4") (pinfunction "4_4") (pintype "passive"))
    )
    (net (code "69") (name "Net-(SW9-Pad3)") (class "Default")
      (node (ref "SW9") (pin "3") (pinfunction "3_3") (pintype "passive"))
      (node (ref "SW9") (pin "6") (pinfunction "6_6") (pintype "passive"))
    )
    (net (code "70") (name "Net-(SW10-Pad1)") (class "Default")
      (node (ref "SW10") (pin "1") (pinfunction "1_1") (pintype "passive"))
      (node (ref "SW10") (pin "4") (pinfunction "4_4") (pintype "passive"))
    )
    (net (code "71") (name "Net-(SW10-Pad3)") (class "Default")
      (node (ref "SW10") (pin "3") (pinfunction "3_3") (pintype "passive"))
      (node (ref "SW10") (pin "6") (pinfunction "6_6") (pintype "passive"))
    )
    (net (code "72") (name "Net-(SW11-Pad1)") (class "Default")
      (node (ref "SW11") (pin "1") (pinfunction "1_1") (pintype "passive"))
      (node (ref "SW11") (pin "4") (pinfunction "4_4") (pintype "passive"))
    )
    (net (code "73") (name "Net-(SW11-Pad3)") (class "Default")
      (node (ref "SW11") (pin "3") (pinfunction "3_3") (pintype "passive"))
      (node (ref "SW11") (pin "6") (pinfunction "6_6") (pintype "passive"))
    )
    (net (code "74") (name "Net-(SW12-Pad1)") (class "Default")
      (node (ref "SW12") (pin "1") (pinfunction "1_1") (pintype "passive"))
      (node (ref "SW12") (pin "4") (pinfunction "4_4") (pintype "passive"))
    )
    (net (code "75") (name "Net-(SW12-Pad3)") (class "Default")
      (node (ref "SW12") (pin "3") (pinfunction "3_3") (pintype "passive"))
      (node (ref "SW12") (pin "6") (pinfunction "6_6") (pintype "passive"))
    )
    (net (code "76") (name "Net-(SW13-Pad1)") (class "Default")
      (node (ref "SW13") (pin "1") (pinfunction "1_1") (pintype "passive"))
      (node (ref "SW13") (pin "4") (pinfunction "4_4") (pintype "passive"))
    )
    (net (code "77") (name "Net-(SW14-Pad1)") (class "Default")
      (node (ref "SW14") (pin "1") (pinfunction "1_1") (pintype "passive"))
      (node (ref "SW14") (pin "4") (pinfunction "4_4") (pintype "passive"))
    )
    (net (code "78") (name "Net-(SW14-Pad3)") (class "Default")
      (node (ref "SW14") (pin "3") (pinfunction "3_3") (pintype "passive"))
      (node (ref "SW14") (pin "6") (pinfunction "6_6") (pintype "passive"))
    )
    (net (code "79") (name "Net-(SW15-Pad1)") (class "Default")
      (node (ref "SW15") (pin "1") (pinfunction "1_1") (pintype "passive"))
      (node (ref "SW15") (pin "4") (pinfunction "4_4") (pintype "passive"))
    )
    (net (code "80") (name "Net-(SW15-Pad3)") (class "Default")
      (node (ref "SW15") (pin "3") (pinfunction "3_3") (pintype "passive"))
      (node (ref "SW15") (pin "6") (pinfunction "6_6") (pintype "passive"))
    )
    (net (code "81") (name "Net-(SW16-Pad1)") (class "Default")
      (node (ref "SW16") (pin "1") (pinfunction "1_1") (pintype "passive"))
      (node (ref "SW16") (pin "4") (pinfunction "4_4") (pintype "passive"))
    )
    (net (code "82") (name "unconnected-(Q7-PadC)") (class "Default")
      (node (ref "Q7") (pin "C") (pinfunction "C_C") (pintype "passive"))
    )
    (net (code "83") (name "unconnected-(SW5-Pad5)") (class "Default")
      (node (ref "SW5") (pin "5") (pinfunction "5_5") (pintype "passive"))
    )
    (net (code "84") (name "unconnected-(SW6-Pad5)") (class "Default")
      (node (ref "SW6") (pin "5") (pinfunction "5_5") (pintype "passive"))
    )
    (net (code "85") (name "unconnected-(SW7-Pad5)") (class "Default")
      (node (ref "SW7") (pin "5") (pinfunction "5_5") (pintype "passive"))
    )
    (net (code "86") (name "unconnected-(SW13-Pad3)") (class "Default")
      (node (ref "SW13") (pin "3") (pinfunction "3_3") (pintype "passive"))
    )
    (net (code "87") (name "unconnected-(SW13-Pad5)") (class "Default")
      (node (ref "SW13") (pin "5") (pinfunction "5_5") (pintype "passive"))
    )
    (net (code "88") (name "unconnected-(SW13-Pad6)") (class "Default")
      (node (ref "SW13") (pin "6") (pinfunction "6_6") (pintype "passive"))
    )
    (net (code "89") (name "unconnected-(SW16-Pad5)") (class "Default")
      (node (ref "SW16") (pin "5") (pinfunction "5_5") (pintype "passive"))
    )
    (net (code "90") (name "unconnected-(SW17-Pad1)") (class "Default")
      (node (ref "SW17") (pin "1") (pinfunction "1_1") (pintype "passive"))
    )
    (net (code "91") (name "unconnected-(SW17-Pad3)") (class "Default")
      (node (ref "SW17") (pin "3") (pinfunction "3_3") (pintype "passive"))
    )
    (net (code "92") (name "unconnected-(SW17-Pad4)") (class "Default")
      (node (ref "SW17") (pin "4") (pinfunction "4_4") (pintype "passive"))
    )
    (net (code "93") (name "unconnected-(SW17-Pad6)") (class "Default")
      (node (ref "SW17") (pin "6") (pinfunction "6_6") (pintype "passive"))
    )
    (net (code "94") (name "unconnected-(SW18-Pad1)") (class "Default")
      (node (ref "SW18") (pin "1") (pinfunction "1_1") (pintype "passive"))
    )
    (net (code "95") (name "unconnected-(SW18-Pad3)") (class "Default")
      (node (ref "SW18") (pin "3") (pinfunction "3_3") (pintype "passive"))
    )
    (net (code "96") (name "unconnected-(SW18-Pad4)") (class "Default")
      (node (ref "SW18") (pin "4") (pinfunction "4_4") (pintype "passive"))
    )
    (net (code "97") (name "unconnected-(SW18-Pad6)") (class "Default")
      (node (ref "SW18") (pin "6") (pinfunction "6_6") (pintype "passive"))
    )
    (net (code "98") (name "unconnected-(SW19-Pad1)") (class "Default")
      (node (ref "SW19") (pin "1") (pinfunction "1_1") (pintype "passive"))
    )
    (net (code "99") (name "unconnected-(SW19-Pad3)") (class "Default")
      (node (ref "SW19") (pin "3") (pinfunction "3_3") (pintype "passive"))
    )
    (net (code "100") (name "unconnected-(SW19-Pad4)") (class "Default")
      (node (ref "SW19") (pin "4") (pinfunction "4_4") (pintype "passive"))
    )
    (net (code "101") (name "unconnected-(SW19-Pad6)") (class "Default")
      (node (ref "SW19") (pin "6") (pinfunction "6_6") (pintype "passive"))
    )
    (net (code "102") (name "unconnected-(SW20-Pad1)") (class "Default")
      (node (ref "SW20") (pin "1") (pinfunction "1_1") (pintype "passive"))
    )
    (net (code "103") (name "unconnected-(SW20-Pad3)") (class "Default")
      (node (ref "SW20") (pin "3") (pinfunction "3_3") (pintype "passive"))
    )
    (net (code "104") (name "unconnected-(SW20-Pad4)") (class "Default")
      (node (ref "SW20") (pin "4") (pinfunction "4_4") (pintype "passive"))
    )
    (net (code "105") (name "unconnected-(SW20-Pad6)") (class "Default")
      (node (ref "SW20") (pin "6") (pinfunction "6_6") (pintype "passive"))
    )
  )
)
